# blink1mk3_micro1a.net
KiCad netlist of a schematic drawn in EAGLE
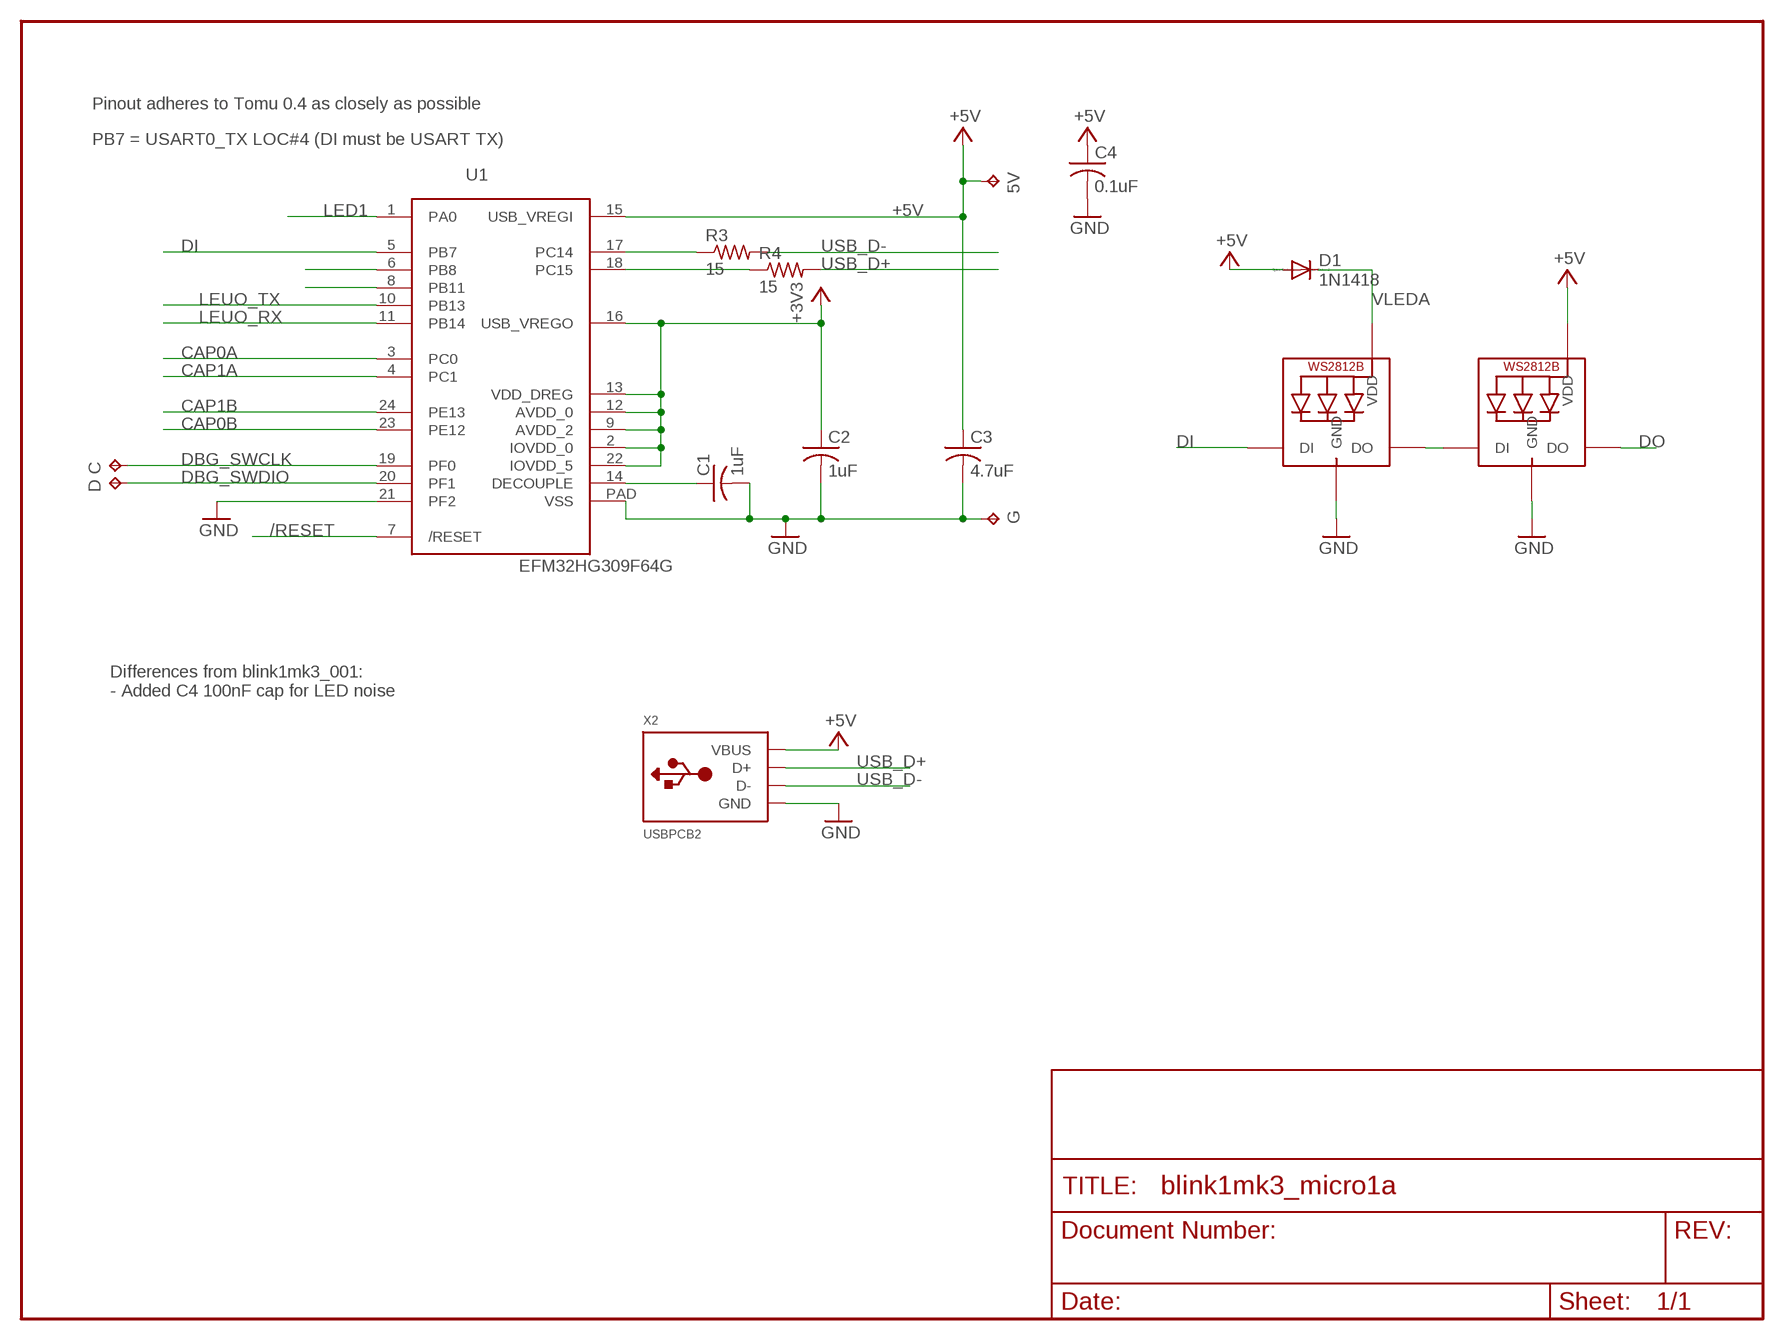
[diagram p0: schematic, sheet 1]

(export (version "E")
  (design (tool "Eeschema 10.0.6"))
  (components
    (comp (ref "5V")
      (value "TPTP10R")
      (footprint "eagle-import:TP10R")
      (libsource (lib "eagle-import") (part "TPTP10R"))
    )
    (comp (ref "C")
      (value "TPTP10R")
      (footprint "eagle-import:TP10R")
      (libsource (lib "eagle-import") (part "TPTP10R"))
    )
    (comp (ref "C1")
      (value "1uF")
      (footprint "eagle-import:C0402")
      (libsource (lib "eagle-import") (part "C-USC0402"))
    )
    (comp (ref "C2")
      (value "1uF")
      (footprint "eagle-import:C0402")
      (libsource (lib "eagle-import") (part "C-USC0402"))
    )
    (comp (ref "C3")
      (value "4.7uF")
      (footprint "eagle-import:C0402")
      (libsource (lib "eagle-import") (part "C-USC0402"))
    )
    (comp (ref "C4")
      (value "0.1uF")
      (footprint "eagle-import:C0402")
      (libsource (lib "eagle-import") (part "C-USC0402"))
    )
    (comp (ref "D")
      (value "TPTP10R")
      (footprint "eagle-import:TP10R")
      (libsource (lib "eagle-import") (part "TPTP10R"))
    )
    (comp (ref "D1")
      (value "1N1418")
      (footprint "eagle-import:SOD523")
      (libsource (lib "eagle-import") (part "DIODE-SOD523"))
    )
    (comp (ref "G")
      (value "TPTP10R")
      (footprint "eagle-import:TP10R")
      (libsource (lib "eagle-import") (part "TPTP10R"))
    )
    (comp (ref "LED1")
      (value "WS2812B4020SIDE")
      (footprint "eagle-import:SK6812-SIDE")
      (libsource (lib "eagle-import") (part "WS2812B4020SIDE"))
    )
    (comp (ref "LED2")
      (value "WS2812B4020SIDE")
      (footprint "eagle-import:SK6812-SIDE")
      (libsource (lib "eagle-import") (part "WS2812B4020SIDE"))
    )
    (comp (ref "R3")
      (value "15")
      (footprint "eagle-import:R0402")
      (libsource (lib "eagle-import") (part "R-US_R0402"))
    )
    (comp (ref "R4")
      (value "15")
      (footprint "eagle-import:R0402")
      (libsource (lib "eagle-import") (part "R-US_R0402"))
    )
    (comp (ref "U1")
      (value "EFM32HG309F64G")
      (footprint "eagle-import:QFN24PAD")
      (libsource (lib "eagle-import") (part "EFM32HG309F64G"))
    )
    (comp (ref "X2")
      (value "USBPCB2")
      (footprint "eagle-import:USB-A-PCB-2")
      (libsource (lib "eagle-import") (part "USBPCB2"))
    )
  )
  (nets
    (net (code "1") (name "+3V3") (class "Default")
      (node (ref "C2") (pin "1") (pinfunction "1_1") (pintype "passive"))
      (node (ref "U1") (pin "12") (pinfunction "AVDD_0_12") (pintype "bidirectional"))
      (node (ref "U1") (pin "13") (pinfunction "VDD_DREG_13") (pintype "bidirectional"))
      (node (ref "U1") (pin "16") (pinfunction "USB_VREGO_16") (pintype "bidirectional"))
      (node (ref "U1") (pin "2") (pinfunction "IOVDD_0_2") (pintype "bidirectional"))
      (node (ref "U1") (pin "22") (pinfunction "IOVDD_5_22") (pintype "bidirectional"))
      (node (ref "U1") (pin "9") (pinfunction "AVDD_2_9") (pintype "bidirectional"))
    )
    (net (code "2") (name "+5V") (class "Default")
      (node (ref "5V") (pin "TP") (pinfunction "TP_TP") (pintype "input"))
      (node (ref "C3") (pin "1") (pinfunction "1_1") (pintype "passive"))
      (node (ref "C4") (pin "1") (pinfunction "1_1") (pintype "passive"))
      (node (ref "D1") (pin "A") (pinfunction "A_A") (pintype "passive"))
      (node (ref "LED2") (pin "1-VDD") (pinfunction "VDD_1-VDD") (pintype "power_in"))
      (node (ref "U1") (pin "15") (pinfunction "USB_VREGI_15") (pintype "bidirectional"))
      (node (ref "X2") (pin "5V") (pinfunction "VBUS_5V") (pintype "power_in"))
    )
    (net (code "3") (name "/CAP0A") (class "Default")
      (node (ref "U1") (pin "3") (pinfunction "PC0_3") (pintype "bidirectional"))
    )
    (net (code "4") (name "/CAP0B") (class "Default")
      (node (ref "U1") (pin "23") (pinfunction "PE12_23") (pintype "bidirectional"))
    )
    (net (code "5") (name "/CAP1A") (class "Default")
      (node (ref "U1") (pin "4") (pinfunction "PC1_4") (pintype "bidirectional"))
    )
    (net (code "6") (name "/CAP1B") (class "Default")
      (node (ref "U1") (pin "24") (pinfunction "PE13_24") (pintype "bidirectional"))
    )
    (net (code "7") (name "/DBG_SWCLK") (class "Default")
      (node (ref "C") (pin "TP") (pinfunction "TP_TP") (pintype "input"))
      (node (ref "U1") (pin "19") (pinfunction "PF0_19") (pintype "bidirectional"))
    )
    (net (code "8") (name "/DBG_SWDIO") (class "Default")
      (node (ref "D") (pin "TP") (pinfunction "TP_TP") (pintype "input"))
      (node (ref "U1") (pin "20") (pinfunction "PF1_20") (pintype "bidirectional"))
    )
    (net (code "9") (name "/DI") (class "Default")
      (node (ref "LED1") (pin "4-DIN") (pinfunction "DI_4-DIN") (pintype "input"))
      (node (ref "U1") (pin "5") (pinfunction "PB7_5") (pintype "bidirectional"))
    )
    (net (code "10") (name "/DO") (class "Default")
      (node (ref "LED2") (pin "2-DOUT") (pinfunction "DO_2-DOUT") (pintype "output"))
    )
    (net (code "11") (name "/LED1") (class "Default")
      (node (ref "U1") (pin "1") (pinfunction "PA0_1") (pintype "bidirectional"))
    )
    (net (code "12") (name "/LEUO_RX") (class "Default")
      (node (ref "U1") (pin "11") (pinfunction "PB14_11") (pintype "bidirectional"))
    )
    (net (code "13") (name "/LEUO_TX") (class "Default")
      (node (ref "U1") (pin "10") (pinfunction "PB13_10") (pintype "bidirectional"))
    )
    (net (code "14") (name "/USB_D+") (class "Default")
      (node (ref "R4") (pin "2") (pinfunction "2_2") (pintype "passive"))
      (node (ref "X2") (pin "USB_P") (pinfunction "D+_USB_P") (pintype "bidirectional"))
    )
    (net (code "15") (name "/USB_D-") (class "Default")
      (node (ref "R3") (pin "2") (pinfunction "2_2") (pintype "passive"))
      (node (ref "X2") (pin "USB_M") (pinfunction "D-_USB_M") (pintype "bidirectional"))
    )
    (net (code "16") (name "/VLEDA") (class "Default")
      (node (ref "D1") (pin "C") (pinfunction "C_C") (pintype "passive"))
      (node (ref "LED1") (pin "1-VDD") (pinfunction "VDD_1-VDD") (pintype "power_in"))
    )
    (net (code "17") (name "/{slash}RESET") (class "Default")
      (node (ref "U1") (pin "7") (pinfunction "/RESET_7") (pintype "bidirectional"))
    )
    (net (code "18") (name "GND") (class "Default")
      (node (ref "C1") (pin "2") (pinfunction "2_2") (pintype "passive"))
      (node (ref "C2") (pin "2") (pinfunction "2_2") (pintype "passive"))
      (node (ref "C3") (pin "2") (pinfunction "2_2") (pintype "passive"))
      (node (ref "C4") (pin "2") (pinfunction "2_2") (pintype "passive"))
      (node (ref "G") (pin "TP") (pinfunction "TP_TP") (pintype "input"))
      (node (ref "LED1") (pin "3-GND") (pinfunction "GND_3-GND") (pintype "power_in"))
      (node (ref "LED2") (pin "3-GND") (pinfunction "GND_3-GND") (pintype "power_in"))
      (node (ref "U1") (pin "21") (pinfunction "PF2_21") (pintype "bidirectional"))
      (node (ref "U1") (pin "PAD") (pinfunction "VSS_PAD") (pintype "bidirectional"))
      (node (ref "X2") (pin "GND") (pinfunction "GND_GND") (pintype "power_in"))
    )
    (net (code "19") (name "Net-(LED1-DO)") (class "Default")
      (node (ref "LED1") (pin "2-DOUT") (pinfunction "DO_2-DOUT") (pintype "output"))
      (node (ref "LED2") (pin "4-DIN") (pinfunction "DI_4-DIN") (pintype "input"))
    )
    (net (code "20") (name "Net-(U1-DECOUPLE)") (class "Default")
      (node (ref "C1") (pin "1") (pinfunction "1_1") (pintype "passive"))
      (node (ref "U1") (pin "14") (pinfunction "DECOUPLE_14") (pintype "bidirectional"))
    )
    (net (code "21") (name "Net-(U1-PC14)") (class "Default")
      (node (ref "R3") (pin "1") (pinfunction "1_1") (pintype "passive"))
      (node (ref "U1") (pin "17") (pinfunction "PC14_17") (pintype "bidirectional"))
    )
    (net (code "22") (name "Net-(U1-PC15)") (class "Default")
      (node (ref "R4") (pin "1") (pinfunction "1_1") (pintype "passive"))
      (node (ref "U1") (pin "18") (pinfunction "PC15_18") (pintype "bidirectional"))
    )
    (net (code "23") (name "unconnected-(U1-PB8-Pad6)") (class "Default")
      (node (ref "U1") (pin "6") (pinfunction "PB8_6") (pintype "bidirectional"))
    )
    (net (code "24") (name "unconnected-(U1-PB11-Pad8)") (class "Default")
      (node (ref "U1") (pin "8") (pinfunction "PB11_8") (pintype "bidirectional"))
    )
  )
)
